# humidity_brick.net
KiCad netlist of a schematic drawn in EAGLE
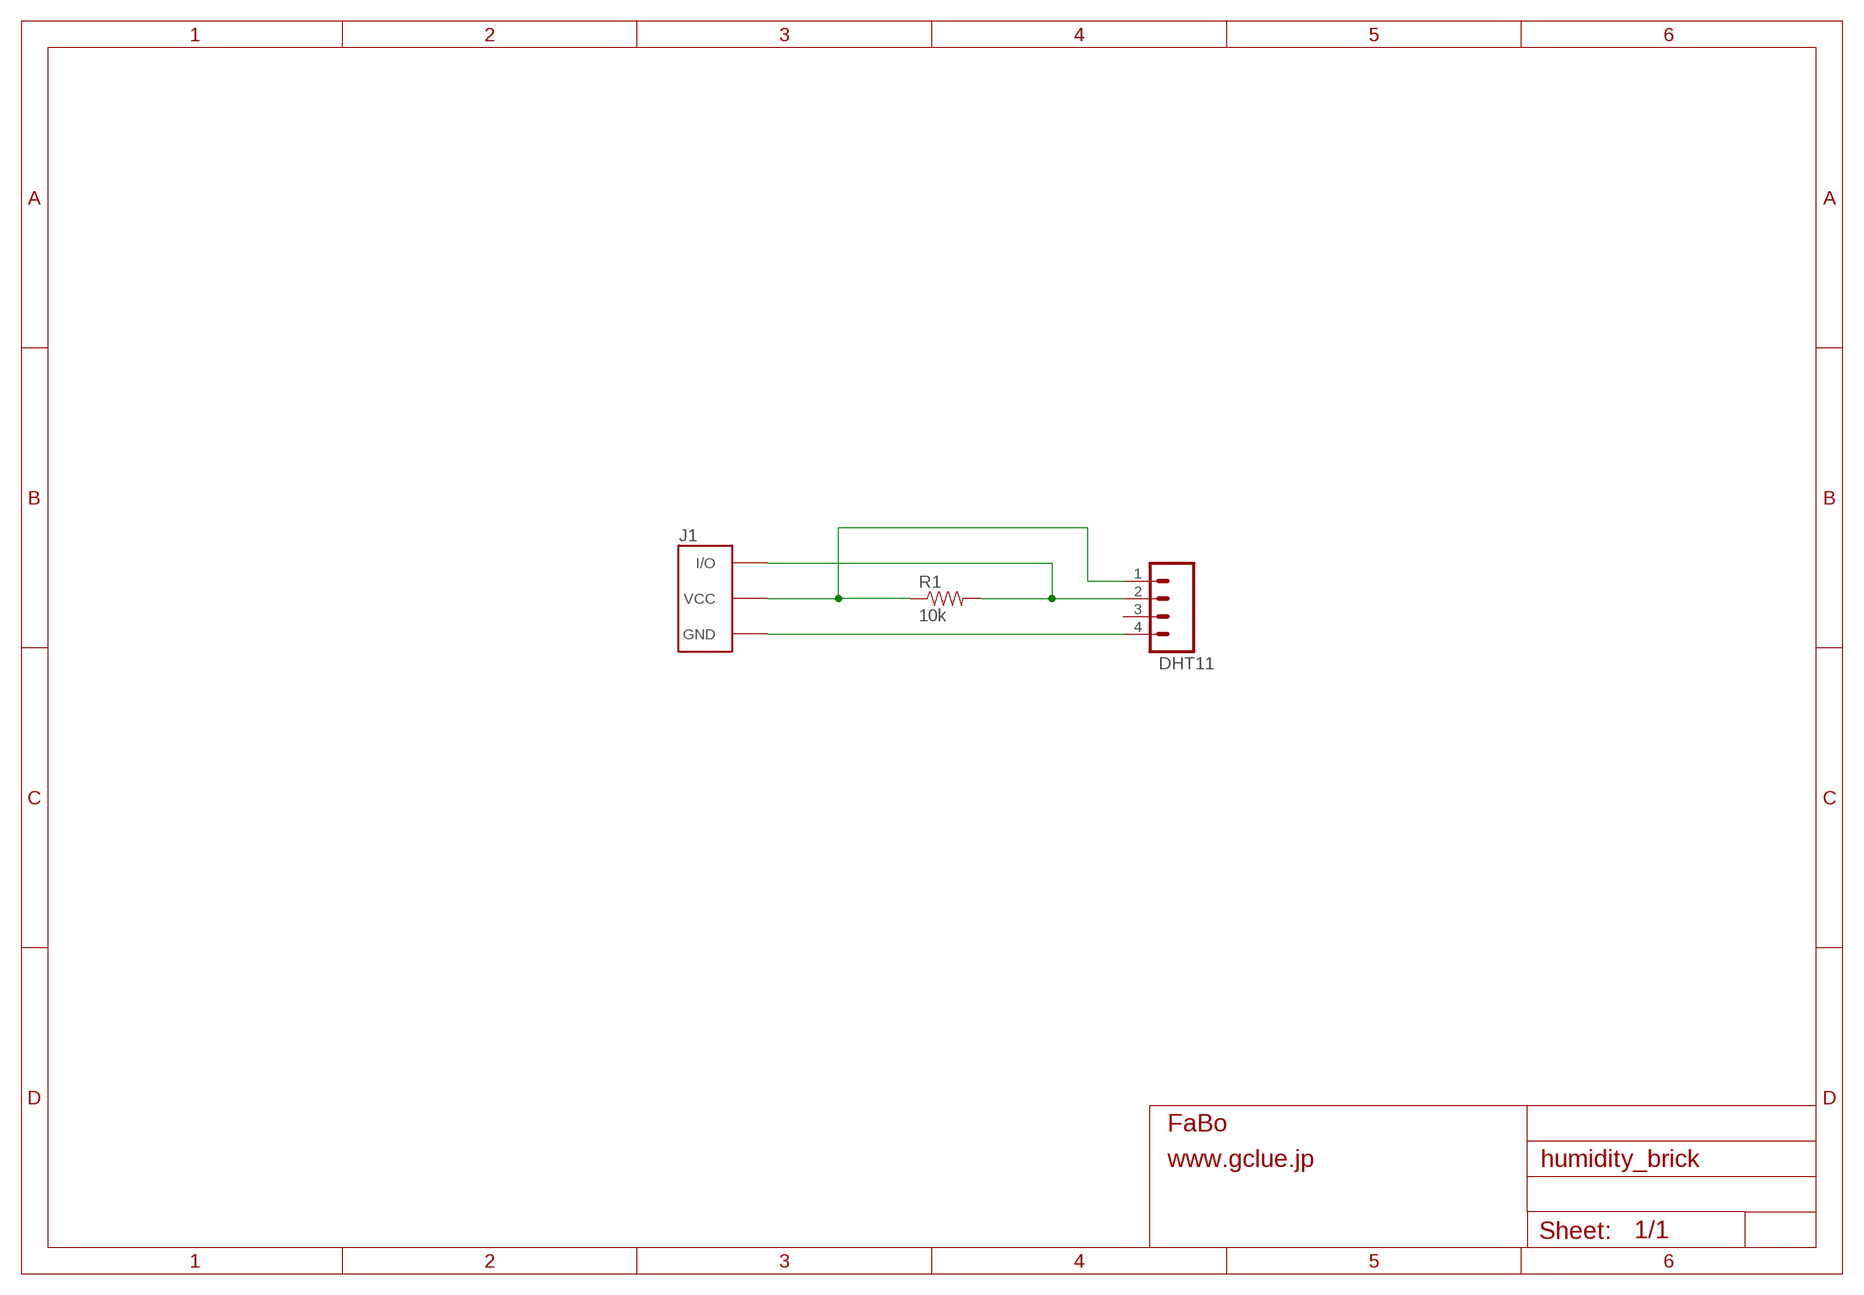
[diagram p0: schematic, sheet 1]

(export (version "E")
  (design (tool "Eeschema 10.0.6"))
  (components
    (comp (ref "J1")
      (value "BRICK_3PIN")
      (footprint "eagle-import:BRICK_3PIN")
      (libsource (lib "eagle-import") (part "BRICK_3PIN"))
    )
    (comp (ref "JP1")
      (value "DHT11")
      (footprint "eagle-import:1X04_LONGPADS")
      (libsource (lib "eagle-import") (part "M04LONGPADS"))
    )
    (comp (ref "R1")
      (value "10k")
      (footprint "eagle-import:AXIAL-0.4")
      (libsource (lib "eagle-import") (part "RESISTORPTH-1/4W"))
    )
  )
  (nets
    (net (code "1") (name "Net-(J1-I{slash}O)") (class "Default")
      (node (ref "J1") (pin "IN/OUT") (pinfunction "I/O_IN/OUT") (pintype "bidirectional"))
      (node (ref "JP1") (pin "2") (pinfunction "2_2") (pintype "passive"))
      (node (ref "R1") (pin "P$2") (pinfunction "2_P$2") (pintype "passive"))
    )
    (net (code "2") (name "Net-(J1-PadGND)") (class "Default")
      (node (ref "J1") (pin "GND") (pinfunction "GND_GND") (pintype "bidirectional"))
      (node (ref "JP1") (pin "4") (pinfunction "4_4") (pintype "passive"))
    )
    (net (code "3") (name "Net-(R1-1)") (class "Default")
      (node (ref "J1") (pin "VCC") (pinfunction "VCC_VCC") (pintype "bidirectional"))
      (node (ref "JP1") (pin "1") (pinfunction "1_1") (pintype "passive"))
      (node (ref "R1") (pin "P$1") (pinfunction "1_P$1") (pintype "passive"))
    )
    (net (code "4") (name "unconnected-(JP1-Pad3)") (class "Default")
      (node (ref "JP1") (pin "3") (pinfunction "3_3") (pintype "passive"))
    )
  )
)
